# Supply.net
KiCad netlist of a schematic drawn in Altium Designer
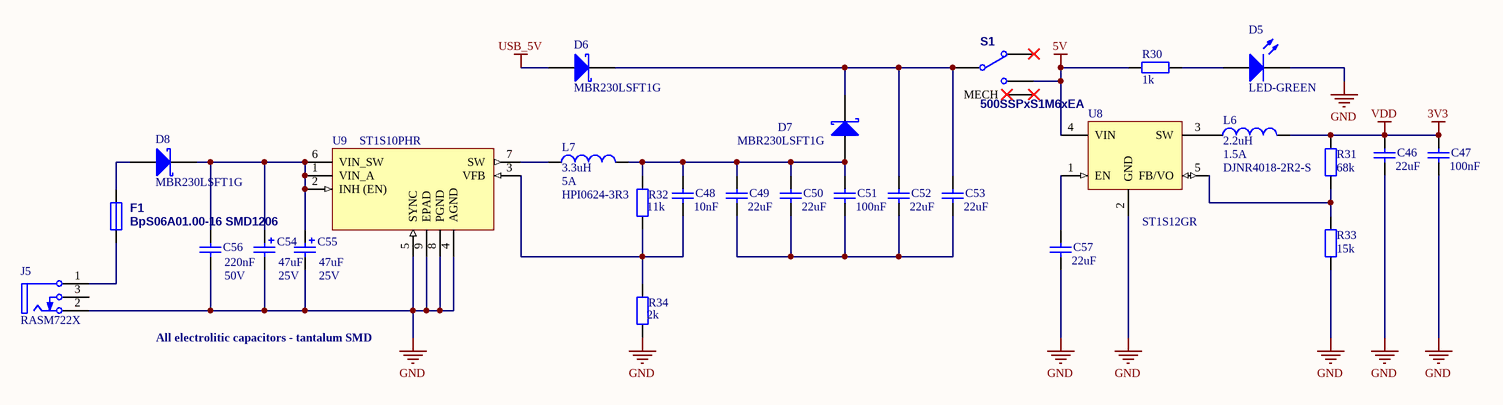
[diagram p0: Supply.SchDoc]

(export (version "E")
  (design (tool "Eeschema 10.0.6"))
  (components
    (comp (ref "C46")
      (value "22uF")
      (footprint "C1206")
      (description "Capacitor")
      (fields (field (name "Comment") "Cap") (field (name "PUBLISHER") "Altium Limited"))
      (libsource (lib "Miscellaneous Devices") (part "Cap"))
    )
    (comp (ref "C47")
      (value "100nF")
      (footprint "C1206")
      (description "Capacitor")
      (fields (field (name "Comment") "Cap") (field (name "PUBLISHER") "Altium Limited"))
      (libsource (lib "Miscellaneous Devices") (part "Cap"))
    )
    (comp (ref "C48")
      (value "10nF")
      (footprint "C1206")
      (description "Capacitor")
      (fields (field (name "Comment") "Cap") (field (name "PUBLISHER") "Altium Limited"))
      (libsource (lib "Miscellaneous Devices") (part "Cap"))
    )
    (comp (ref "C49")
      (value "22uF")
      (footprint "C1206")
      (description "Capacitor")
      (fields (field (name "Comment") "Cap") (field (name "PUBLISHER") "Altium Limited"))
      (libsource (lib "Miscellaneous Devices") (part "Cap"))
    )
    (comp (ref "C50")
      (value "22uF")
      (footprint "C1206")
      (description "Capacitor")
      (fields (field (name "Comment") "Cap") (field (name "PUBLISHER") "Altium Limited"))
      (libsource (lib "Miscellaneous Devices") (part "Cap"))
    )
    (comp (ref "C51")
      (value "100nF")
      (footprint "C1206")
      (description "Capacitor")
      (fields (field (name "Comment") "Cap") (field (name "PUBLISHER") "Altium Limited"))
      (libsource (lib "Miscellaneous Devices") (part "Cap"))
    )
    (comp (ref "C52")
      (value "22uF")
      (footprint "C1206")
      (description "Capacitor")
      (fields (field (name "Comment") "Cap") (field (name "PUBLISHER") "Altium Limited"))
      (libsource (lib "Miscellaneous Devices") (part "Cap"))
    )
    (comp (ref "C53")
      (value "22uF")
      (footprint "C1206")
      (description "Capacitor")
      (fields (field (name "Comment") "Cap") (field (name "PUBLISHER") "Altium Limited"))
      (libsource (lib "Miscellaneous Devices") (part "Cap"))
    )
    (comp (ref "C54")
      (value "25V")
      (footprint "SMDB")
      (description "Polarized Capacitor (Axial)")
      (fields (field (name "ALTIUM_VALUE") "47uF") (field (name "PUBLISHER") "Altium Limited"))
      (libsource (lib "Miscellaneous Devices") (part "Cap Pol2"))
    )
    (comp (ref "C55")
      (value "25V")
      (footprint "SMDB")
      (description "Polarized Capacitor (Axial)")
      (fields (field (name "ALTIUM_VALUE") "47uF") (field (name "PUBLISHER") "Altium Limited"))
      (libsource (lib "Miscellaneous Devices") (part "Cap Pol2"))
    )
    (comp (ref "C56")
      (value "50V")
      (footprint "C1206")
      (description "Capacitor")
      (fields (field (name "ALTIUM_VALUE") "220nF") (field (name "PUBLISHER") "Altium Limited"))
      (libsource (lib "Miscellaneous Devices") (part "Cap"))
    )
    (comp (ref "C57")
      (value "22uF")
      (footprint "C1206")
      (description "Capacitor")
      (fields (field (name "Comment") "Cap") (field (name "PUBLISHER") "Altium Limited"))
      (libsource (lib "Miscellaneous Devices") (part "Cap"))
    )
    (comp (ref "D5")
      (value "LED-GREEN")
      (footprint "LED0603G")
      (description "Typical INFRARED GaAs LED")
      (fields (field (name "PUBLISHER") "Altium Limited"))
      (libsource (lib "Miscellaneous Devices") (part "LED0"))
    )
    (comp (ref "D6")
      (value "MBR230LSFT1G")
      (footprint "SMB")
      (description "Schottky Diode")
      (fields (field (name "PUBLISHER") "Altium Limited"))
      (libsource (lib "Miscellaneous Devices") (part "D Schottky"))
    )
    (comp (ref "D7")
      (value "MBR230LSFT1G")
      (footprint "SMB")
      (description "Schottky Diode")
      (fields (field (name "PUBLISHER") "Altium Limited"))
      (libsource (lib "Miscellaneous Devices") (part "D Schottky"))
    )
    (comp (ref "D8")
      (value "MBR230LSFT1G")
      (footprint "SMB")
      (description "Schottky Diode")
      (fields (field (name "PUBLISHER") "Altium Limited"))
      (libsource (lib "Miscellaneous Devices") (part "D Schottky"))
    )
    (comp (ref "F1")
      (value "BpS06A01.00-16 SMD1206")
      (footprint "F1206")
      (fields (field (name "PUBLISHER") "Altium Limited"))
      (libsource (lib "fuses") (part "1206 Fuse"))
    )
    (comp (ref "J5")
      (value "RASM722X")
      (footprint "SWIT-RASM722X_V")
      (description "Power Jack, 5 A, 250 V, 3-Pin SMD, RoHS, Bulk")
      (libsource (lib "schematy") (part "JACK-2CD3-TN"))
    )
    (comp (ref "L6")
      (value "DJNR4018-2R2-S")
      (footprint "L2220_3")
      (description "Inductor")
      (fields
        (field (name "ALTIUM_VALUE") "2.2uH")
        (field (name "VALUE2") "1.5A")
        (field (name "PUBLISHER") "Altium Limited")
      )
      (libsource (lib "Miscellaneous Devices") (part "Inductor"))
    )
    (comp (ref "L7")
      (value "HPI0624-3R3")
      (footprint "DE0703")
      (description "Inductor")
      (fields
        (field (name "ALTIUM_VALUE") "3.3uH")
        (field (name "VALUE2") "5A")
        (field (name "PUBLISHER") "Altium Limited")
      )
      (libsource (lib "Miscellaneous Devices") (part "Inductor"))
    )
    (comp (ref "R30")
      (value "1k")
      (footprint "6-0805_L")
      (description "Resistor")
      (fields (field (name "Comment") "Res2") (field (name "PUBLISHER") "Altium Limited"))
      (libsource (lib "") (part "Res2_1"))
    )
    (comp (ref "R31")
      (value "68k")
      (footprint "6-0805_L")
      (description "Resistor")
      (fields (field (name "Comment") "Res2") (field (name "PUBLISHER") "Altium Limited"))
      (libsource (lib "Miscellaneous Devices") (part "Res2"))
    )
    (comp (ref "R32")
      (value "11k")
      (footprint "6-0805_L")
      (description "Resistor")
      (fields (field (name "Comment") "Res2") (field (name "PUBLISHER") "Altium Limited"))
      (libsource (lib "Miscellaneous Devices") (part "Res2"))
    )
    (comp (ref "R33")
      (value "15k")
      (footprint "6-0805_L")
      (description "Resistor")
      (fields (field (name "Comment") "Res2") (field (name "PUBLISHER") "Altium Limited"))
      (libsource (lib "Miscellaneous Devices") (part "Res2"))
    )
    (comp (ref "R34")
      (value "2k")
      (footprint "6-0805_L")
      (description "Resistor")
      (fields (field (name "Comment") "Res2") (field (name "PUBLISHER") "Altium Limited"))
      (libsource (lib "Miscellaneous Devices") (part "Res2"))
    )
    (comp (ref "S1")
      (value "500SSPxS1M6xEA")
      (footprint "500SSPxS1M6xEA")
      (description "E-Switches SPDT AC: 3A/250V, DC: 6A/28V")
      (libsource (lib "switches_slide") (part "500SSPxS1M6xEA"))
    )
    (comp (ref "U8")
      (value "ST1S12GR")
      (footprint "TSOT23-5L_L")
      (libsource (lib "schematy") (part "PM-SWREG-ST1S12G-IL5"))
    )
    (comp (ref "U9")
      (value "ST1S10PHR")
      (footprint "HSO-8_L")
      (description "Monolithic synchronous step-down regulator, 8-Pin HSOP, Tape and Reel")
      (libsource (lib "schematy") (part "PM-REG-ST1S10-IL9"))
    )
  )
  (nets
    (net (code "1") (name "3V3") (class "Default")
      (node (ref "C46") (pin "2") (pinfunction "2_2") (pintype "passive"))
      (node (ref "C47") (pin "2") (pinfunction "2_2") (pintype "passive"))
      (node (ref "L6") (pin "2") (pinfunction "2_2") (pintype "passive"))
      (node (ref "R31") (pin "2") (pinfunction "2_2") (pintype "passive"))
    )
    (net (code "2") (name "5V") (class "Default")
      (node (ref "R30") (pin "1") (pinfunction "1_1") (pintype "passive"))
      (node (ref "S1") (pin "3") (pinfunction "3_3") (pintype "passive"))
      (node (ref "U8") (pin "4") (pinfunction "VIN_4") (pintype "power_in"))
    )
    (net (code "3") (name "GND") (class "Default")
      (node (ref "C46") (pin "1") (pinfunction "1_1") (pintype "passive"))
      (node (ref "C47") (pin "1") (pinfunction "1_1") (pintype "passive"))
      (node (ref "C54") (pin "2") (pinfunction "2_2") (pintype "passive"))
      (node (ref "C55") (pin "2") (pinfunction "2_2") (pintype "passive"))
      (node (ref "C56") (pin "1") (pinfunction "1_1") (pintype "passive"))
      (node (ref "C57") (pin "1") (pinfunction "1_1") (pintype "passive"))
      (node (ref "D5") (pin "2") (pinfunction "K_2") (pintype "passive"))
      (node (ref "J5") (pin "2") (pinfunction "TIP_2") (pintype "passive"))
      (node (ref "R33") (pin "1") (pinfunction "1_1") (pintype "passive"))
      (node (ref "R34") (pin "1") (pinfunction "1_1") (pintype "passive"))
      (node (ref "U8") (pin "2") (pinfunction "GND_2") (pintype "power_in"))
      (node (ref "U9") (pin "4") (pinfunction "AGND_4") (pintype "power_in"))
      (node (ref "U9") (pin "5") (pinfunction "SYNC_5") (pintype "input"))
      (node (ref "U9") (pin "8") (pinfunction "PGND_8") (pintype "power_in"))
      (node (ref "U9") (pin "9") (pinfunction "EPAD_9") (pintype "power_in"))
    )
    (net (code "4") (name "Net-(C49-Pad1)") (class "Default")
      (node (ref "C49") (pin "1") (pinfunction "1_1") (pintype "passive"))
      (node (ref "C50") (pin "1") (pinfunction "1_1") (pintype "passive"))
      (node (ref "C51") (pin "1") (pinfunction "1_1") (pintype "passive"))
      (node (ref "C52") (pin "1") (pinfunction "1_1") (pintype "passive"))
      (node (ref "C53") (pin "1") (pinfunction "1_1") (pintype "passive"))
    )
    (net (code "5") (name "Net-(D5-A)") (class "Default")
      (node (ref "D5") (pin "1") (pinfunction "A_1") (pintype "passive"))
      (node (ref "R30") (pin "2") (pinfunction "2_2") (pintype "passive"))
    )
    (net (code "6") (name "Net-(D6-K)") (class "Default")
      (node (ref "C52") (pin "2") (pinfunction "2_2") (pintype "passive"))
      (node (ref "C53") (pin "2") (pinfunction "2_2") (pintype "passive"))
      (node (ref "D6") (pin "2") (pinfunction "K_2") (pintype "passive"))
      (node (ref "D7") (pin "2") (pinfunction "K_2") (pintype "passive"))
      (node (ref "S1") (pin "2") (pinfunction "2_2") (pintype "passive"))
    )
    (net (code "7") (name "Net-(D7-A)") (class "Default")
      (node (ref "C48") (pin "2") (pinfunction "2_2") (pintype "passive"))
      (node (ref "C49") (pin "2") (pinfunction "2_2") (pintype "passive"))
      (node (ref "C50") (pin "2") (pinfunction "2_2") (pintype "passive"))
      (node (ref "C51") (pin "2") (pinfunction "2_2") (pintype "passive"))
      (node (ref "D7") (pin "1") (pinfunction "A_1") (pintype "passive"))
      (node (ref "L7") (pin "2") (pinfunction "2_2") (pintype "passive"))
      (node (ref "R32") (pin "2") (pinfunction "2_2") (pintype "passive"))
    )
    (net (code "8") (name "Net-(D8-A)") (class "Default")
      (node (ref "D8") (pin "1") (pinfunction "A_1") (pintype "passive"))
      (node (ref "F1") (pin "2") (pinfunction "2_2") (pintype "passive"))
    )
    (net (code "9") (name "Net-(D8-K)") (class "Default")
      (node (ref "C54") (pin "1") (pinfunction "1_1") (pintype "passive"))
      (node (ref "C55") (pin "1") (pinfunction "1_1") (pintype "passive"))
      (node (ref "C56") (pin "2") (pinfunction "2_2") (pintype "passive"))
      (node (ref "D8") (pin "2") (pinfunction "K_2") (pintype "passive"))
      (node (ref "U9") (pin "1") (pinfunction "VIN_A_1") (pintype "power_in"))
      (node (ref "U9") (pin "2") (pinfunction "INH_(EN)_2") (pintype "input"))
      (node (ref "U9") (pin "6") (pinfunction "VIN_SW_6") (pintype "power_in"))
    )
    (net (code "10") (name "Net-(J5-SLEEVE)") (class "Default")
      (node (ref "F1") (pin "1") (pinfunction "1_1") (pintype "passive"))
      (node (ref "J5") (pin "1") (pinfunction "SLEEVE_1") (pintype "passive"))
    )
    (net (code "11") (name "Net-(U8-EN)") (class "Default")
      (node (ref "C57") (pin "2") (pinfunction "2_2") (pintype "passive"))
      (node (ref "U8") (pin "1") (pinfunction "EN_1") (pintype "input"))
    )
    (net (code "12") (name "Net-(U8-FB{slash}VO)") (class "Default")
      (node (ref "R31") (pin "1") (pinfunction "1_1") (pintype "passive"))
      (node (ref "R33") (pin "2") (pinfunction "2_2") (pintype "passive"))
      (node (ref "U8") (pin "5") (pinfunction "FB/VO_5") (pintype "bidirectional"))
    )
    (net (code "13") (name "Net-(U8-SW)") (class "Default")
      (node (ref "L6") (pin "1") (pinfunction "1_1") (pintype "passive"))
      (node (ref "U8") (pin "3") (pinfunction "SW_3") (pintype "power_in"))
    )
    (net (code "14") (name "Net-(U9-SW)") (class "Default")
      (node (ref "L7") (pin "1") (pinfunction "1_1") (pintype "passive"))
      (node (ref "U9") (pin "7") (pinfunction "SW_7") (pintype "output"))
    )
    (net (code "15") (name "Net-(U9-VFB)") (class "Default")
      (node (ref "C48") (pin "1") (pinfunction "1_1") (pintype "passive"))
      (node (ref "R32") (pin "1") (pinfunction "1_1") (pintype "passive"))
      (node (ref "R34") (pin "2") (pinfunction "2_2") (pintype "passive"))
      (node (ref "U9") (pin "3") (pinfunction "VFB_3") (pintype "input"))
    )
    (net (code "16") (name "USB_5V") (class "Default")
      (node (ref "D6") (pin "1") (pinfunction "A_1") (pintype "passive"))
    )
    (net (code "17") (name "unconnected-(J5-SHUNT-Pad3)") (class "Default")
      (node (ref "J5") (pin "3") (pinfunction "SHUNT_3") (pintype "passive"))
    )
    (net (code "18") (name "unconnected-(S1-MECH-PadM)") (class "Default")
      (node (ref "S1") (pin "M") (pinfunction "MECH_M") (pintype "passive+no_connect"))
    )
    (net (code "19") (name "unconnected-(S1-Pad1)") (class "Default")
      (node (ref "S1") (pin "1") (pinfunction "1_1") (pintype "passive+no_connect"))
    )
  )
)
